# design.net
KiCad netlist of a schematic drawn in Altium Designer
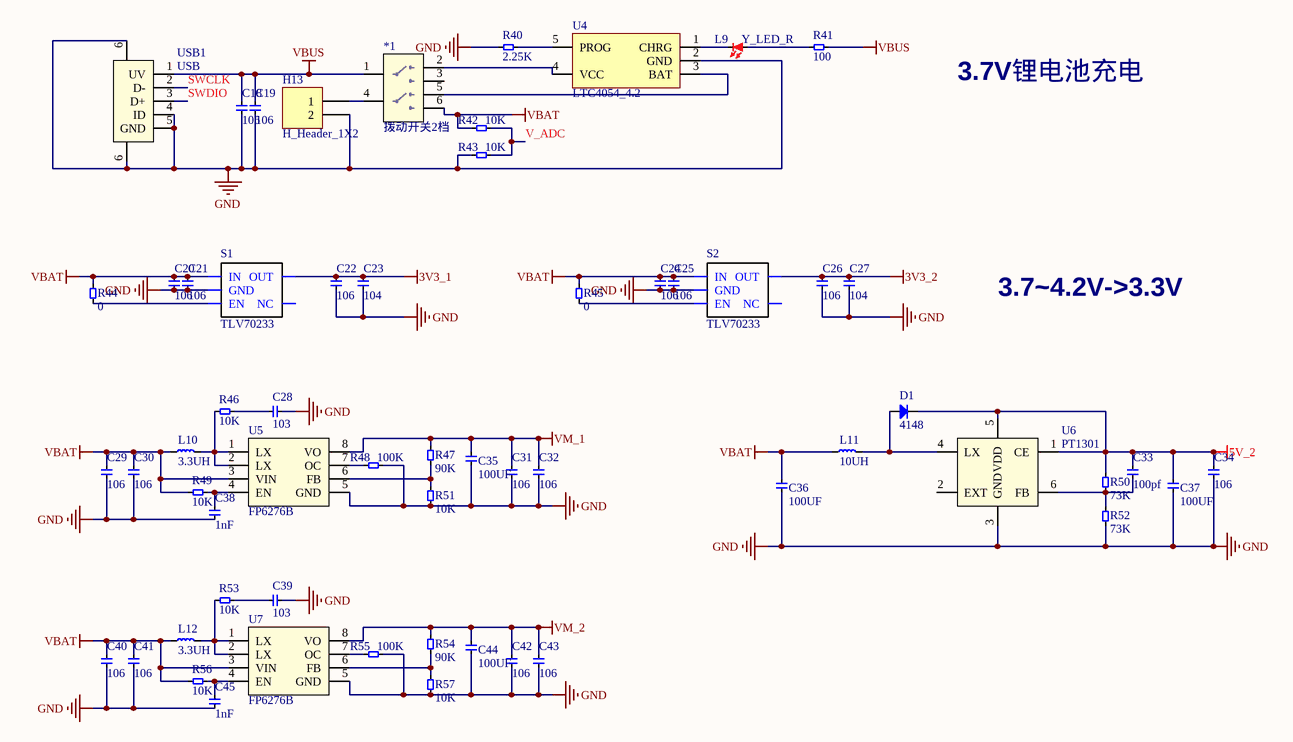
[diagram p0: 电源.SchDoc]

(export (version "E")
  (design (tool "Eeschema 10.0.6"))
  (components
    (comp (ref "*1") (value "拨动开关2档") (footprint "拨档开关2x3立式") (libsource (lib "王建勇") (part "拨动开关2档")))
    (comp (ref "C18")
      (value "106")
      (footprint "C_0603")
      (description "无极性贴片电容")
      (libsource (lib "电阻电容电感库") (part "C_无极贴片"))
    )
    (comp (ref "C19")
      (value "106")
      (footprint "C_0603")
      (description "无极性贴片电容")
      (libsource (lib "电阻电容电感库") (part "C_无极贴片"))
    )
    (comp (ref "C20")
      (value "106")
      (footprint "C_0603")
      (description "无极性贴片电容")
      (libsource (lib "电阻电容电感库") (part "C_无极贴片"))
    )
    (comp (ref "C21")
      (value "106")
      (footprint "C_0603")
      (description "无极性贴片电容")
      (libsource (lib "电阻电容电感库") (part "C_无极贴片"))
    )
    (comp (ref "C22")
      (value "106")
      (footprint "C_0603")
      (description "无极性贴片电容")
      (libsource (lib "电阻电容电感库") (part "C_无极贴片"))
    )
    (comp (ref "C23")
      (value "104")
      (footprint "C_0603")
      (description "无极性贴片电容")
      (libsource (lib "电阻电容电感库") (part "C_无极贴片"))
    )
    (comp (ref "C24")
      (value "106")
      (footprint "C_0603")
      (description "无极性贴片电容")
      (libsource (lib "电阻电容电感库") (part "C_无极贴片"))
    )
    (comp (ref "C25")
      (value "106")
      (footprint "C_0603")
      (description "无极性贴片电容")
      (libsource (lib "电阻电容电感库") (part "C_无极贴片"))
    )
    (comp (ref "C26")
      (value "106")
      (footprint "C_0603")
      (description "无极性贴片电容")
      (libsource (lib "电阻电容电感库") (part "C_无极贴片"))
    )
    (comp (ref "C27")
      (value "104")
      (footprint "C_0603")
      (description "无极性贴片电容")
      (libsource (lib "电阻电容电感库") (part "C_无极贴片"))
    )
    (comp (ref "C28")
      (value "103")
      (footprint "C_0603")
      (description "无极性贴片电容")
      (libsource (lib "电阻电容电感库") (part "C_无极贴片"))
    )
    (comp (ref "C29")
      (value "106")
      (footprint "C_0603")
      (description "无极性贴片电容")
      (libsource (lib "电阻电容电感库") (part "C_无极贴片"))
    )
    (comp (ref "C30")
      (value "106")
      (footprint "C_0603")
      (description "无极性贴片电容")
      (libsource (lib "电阻电容电感库") (part "C_无极贴片"))
    )
    (comp (ref "C31")
      (value "106")
      (footprint "C_0603")
      (description "无极性贴片电容")
      (libsource (lib "电阻电容电感库") (part "C_无极贴片"))
    )
    (comp (ref "C32")
      (value "106")
      (footprint "C_0603")
      (description "无极性贴片电容")
      (libsource (lib "电阻电容电感库") (part "C_无极贴片"))
    )
    (comp (ref "C33")
      (value "100pf")
      (footprint "C_0603")
      (description "无极性贴片电容")
      (libsource (lib "电阻电容电感库") (part "C_无极贴片"))
    )
    (comp (ref "C34")
      (value "106")
      (footprint "C_0603")
      (description "无极性贴片电容")
      (libsource (lib "电阻电容电感库") (part "C_无极贴片"))
    )
    (comp (ref "C35")
      (value "100UF")
      (footprint "C_1210")
      (description "无极性贴片电容")
      (libsource (lib "电阻电容电感库") (part "C_无极贴片"))
    )
    (comp (ref "C36")
      (value "100UF")
      (footprint "C_1210")
      (description "无极性贴片电容")
      (libsource (lib "电阻电容电感库") (part "C_无极贴片"))
    )
    (comp (ref "C37")
      (value "100UF")
      (footprint "C_1210")
      (description "无极性贴片电容")
      (libsource (lib "电阻电容电感库") (part "C_无极贴片"))
    )
    (comp (ref "C38")
      (value "1nF")
      (footprint "C_0603")
      (description "无极性贴片电容")
      (libsource (lib "电阻电容电感库") (part "C_无极贴片"))
    )
    (comp (ref "C39")
      (value "103")
      (footprint "C_0603")
      (description "无极性贴片电容")
      (libsource (lib "电阻电容电感库") (part "C_无极贴片"))
    )
    (comp (ref "C40")
      (value "106")
      (footprint "C_0603")
      (description "无极性贴片电容")
      (libsource (lib "电阻电容电感库") (part "C_无极贴片"))
    )
    (comp (ref "C41")
      (value "106")
      (footprint "C_0603")
      (description "无极性贴片电容")
      (libsource (lib "电阻电容电感库") (part "C_无极贴片"))
    )
    (comp (ref "C42")
      (value "106")
      (footprint "C_0603")
      (description "无极性贴片电容")
      (libsource (lib "电阻电容电感库") (part "C_无极贴片"))
    )
    (comp (ref "C43")
      (value "106")
      (footprint "C_0603")
      (description "无极性贴片电容")
      (libsource (lib "电阻电容电感库") (part "C_无极贴片"))
    )
    (comp (ref "C44")
      (value "100UF")
      (footprint "C_1210")
      (description "无极性贴片电容")
      (libsource (lib "电阻电容电感库") (part "C_无极贴片"))
    )
    (comp (ref "C45")
      (value "1nF")
      (footprint "C_0603")
      (description "无极性贴片电容")
      (libsource (lib "电阻电容电感库") (part "C_无极贴片"))
    )
    (comp (ref "D1")
      (value "4148")
      (footprint "1206D")
      (libsource (lib "lucifer-PCBLIB_V2.0（这是老蒋的）") (part "diode 4148"))
    )
    (comp (ref "H13")
      (value "H_Header_1X2")
      (footprint "H_Header_1X2")
      (description "单排2针排针")
      (fields (field (name "PUBLISHER") "Altium Limited"))
      (libsource (lib "接插件") (part "H_Header_1X2"))
    )
    (comp (ref "L9")
      (value "Y_LED_R")
      (footprint "Y_LED_0805_R")
      (description "红色LED")
      (libsource (lib "声光元件") (part "Y_LED_R"))
    )
    (comp (ref "L10")
      (value "3.3UH")
      (footprint "L_VISHAY_IHLP-1616")
      (description "贴片屏蔽式功率电感")
      (libsource (lib "电阻电容电感库") (part "L_贴片功率"))
    )
    (comp (ref "L11")
      (value "10UH")
      (footprint "L_VISHAY_IHLP-1616")
      (description "贴片屏蔽式功率电感")
      (libsource (lib "电阻电容电感库") (part "L_贴片功率"))
    )
    (comp (ref "L12")
      (value "3.3UH")
      (footprint "L_VISHAY_IHLP-1616")
      (description "贴片屏蔽式功率电感")
      (libsource (lib "电阻电容电感库") (part "L_贴片功率"))
    )
    (comp (ref "R40")
      (value "2.25K")
      (footprint "R_0603")
      (description "贴片电阻")
      (libsource (lib "电阻电容电感库") (part "R_贴片"))
    )
    (comp (ref "R41")
      (value "100")
      (footprint "R_0603")
      (description "贴片电阻")
      (libsource (lib "电阻电容电感库") (part "R_贴片"))
    )
    (comp (ref "R42")
      (value "10K")
      (footprint "R_0603")
      (description "贴片电阻")
      (libsource (lib "电阻电容电感库") (part "R_贴片"))
    )
    (comp (ref "R43")
      (value "10K")
      (footprint "R_0603")
      (description "贴片电阻")
      (libsource (lib "电阻电容电感库") (part "R_贴片"))
    )
    (comp (ref "R44")
      (value "0")
      (footprint "R_0603")
      (description "贴片电阻")
      (libsource (lib "电阻电容电感库") (part "R_贴片"))
    )
    (comp (ref "R45")
      (value "0")
      (footprint "R_0603")
      (description "贴片电阻")
      (libsource (lib "电阻电容电感库") (part "R_贴片"))
    )
    (comp (ref "R46")
      (value "10K")
      (footprint "R_0603")
      (description "贴片电阻")
      (libsource (lib "电阻电容电感库") (part "R_贴片"))
    )
    (comp (ref "R47")
      (value "90K")
      (footprint "R_0603")
      (description "贴片电阻")
      (libsource (lib "电阻电容电感库") (part "R_贴片"))
    )
    (comp (ref "R48")
      (value "100K")
      (footprint "R_0603")
      (description "贴片电阻")
      (libsource (lib "电阻电容电感库") (part "R_贴片"))
    )
    (comp (ref "R49")
      (value "10K")
      (footprint "R_0603")
      (description "贴片电阻")
      (libsource (lib "电阻电容电感库") (part "R_贴片"))
    )
    (comp (ref "R50")
      (value "73K")
      (footprint "R_0603")
      (description "贴片电阻")
      (libsource (lib "电阻电容电感库") (part "R_贴片"))
    )
    (comp (ref "R51")
      (value "10K")
      (footprint "R_0603")
      (description "贴片电阻")
      (libsource (lib "电阻电容电感库") (part "R_贴片"))
    )
    (comp (ref "R52")
      (value "73K")
      (footprint "R_0603")
      (description "贴片电阻")
      (libsource (lib "电阻电容电感库") (part "R_贴片"))
    )
    (comp (ref "R53")
      (value "10K")
      (footprint "R_0603")
      (description "贴片电阻")
      (libsource (lib "电阻电容电感库") (part "R_贴片"))
    )
    (comp (ref "R54")
      (value "90K")
      (footprint "R_0603")
      (description "贴片电阻")
      (libsource (lib "电阻电容电感库") (part "R_贴片"))
    )
    (comp (ref "R55")
      (value "100K")
      (footprint "R_0603")
      (description "贴片电阻")
      (libsource (lib "电阻电容电感库") (part "R_贴片"))
    )
    (comp (ref "R56")
      (value "10K")
      (footprint "R_0603")
      (description "贴片电阻")
      (libsource (lib "电阻电容电感库") (part "R_贴片"))
    )
    (comp (ref "R57")
      (value "10K")
      (footprint "R_0603")
      (description "贴片电阻")
      (libsource (lib "电阻电容电感库") (part "R_贴片"))
    )
    (comp (ref "S1")
      (value "TLV70233")
      (footprint "S_SOT23-5_TLV70233")
      (description "小封装LDO")
      (libsource (lib "电源") (part "S_TLV70233"))
    )
    (comp (ref "S2")
      (value "TLV70233")
      (footprint "S_SOT23-5_TLV70233")
      (description "小封装LDO")
      (libsource (lib "电源") (part "S_TLV70233"))
    )
    (comp (ref "U4") (value "LTC4054_4.2") (footprint "PDSO_G5") (libsource (lib "王建勇") (part "LTC4054_4.2")))
    (comp (ref "U5") (value "FP6276B") (footprint "SOP8") (libsource (lib "王建勇") (part "FP6267B")))
    (comp (ref "U6") (value "PT1301") (footprint "PDSO_G6") (libsource (lib "王建勇") (part "PT1301")))
    (comp (ref "U7") (value "FP6276B") (footprint "SOP8") (libsource (lib "王建勇") (part "FP6267B")))
    (comp (ref "USB1") (value "USB") (footprint "micro-USB(立式直插）") (libsource (lib "王建勇") (part "USB")))
  )
  (nets
    (net (code "1") (name "/SWCLK") (class "Default")
      (node (ref "USB1") (pin "2") (pinfunction "D-_2") (pintype "passive"))
    )
    (net (code "2") (name "/SWDIO") (class "Default")
      (node (ref "USB1") (pin "3") (pinfunction "D+_3") (pintype "passive"))
    )
    (net (code "3") (name "/V_ADC") (class "Default")
      (node (ref "R42") (pin "2") (pintype "passive"))
      (node (ref "R43") (pin "2") (pintype "passive"))
    )
    (net (code "4") (name "3V3_1") (class "Default")
      (node (ref "C22") (pin "2") (pinfunction "2_2") (pintype "passive"))
      (node (ref "C23") (pin "2") (pinfunction "2_2") (pintype "passive"))
      (node (ref "S1") (pin "5") (pinfunction "OUT_5") (pintype "passive"))
    )
    (net (code "5") (name "3V3_2") (class "Default")
      (node (ref "C26") (pin "2") (pinfunction "2_2") (pintype "passive"))
      (node (ref "C27") (pin "2") (pinfunction "2_2") (pintype "passive"))
      (node (ref "S2") (pin "5") (pinfunction "OUT_5") (pintype "passive"))
    )
    (net (code "6") (name "5V_2") (class "Default")
      (node (ref "C33") (pin "2") (pinfunction "2_2") (pintype "passive"))
      (node (ref "C34") (pin "2") (pinfunction "2_2") (pintype "passive"))
      (node (ref "C37") (pin "2") (pinfunction "2_2") (pintype "passive"))
      (node (ref "D1") (pin "2") (pinfunction "K_2") (pintype "passive"))
      (node (ref "R50") (pin "2") (pintype "passive"))
      (node (ref "U6") (pin "1") (pinfunction "CE_1") (pintype "passive"))
      (node (ref "U6") (pin "5") (pinfunction "VDD_5") (pintype "passive"))
    )
    (net (code "7") (name "GND") (class "Default")
      (node (ref "C18") (pin "1") (pinfunction "1_1") (pintype "passive"))
      (node (ref "C19") (pin "1") (pinfunction "1_1") (pintype "passive"))
      (node (ref "C20") (pin "1") (pinfunction "1_1") (pintype "passive"))
      (node (ref "C21") (pin "1") (pinfunction "1_1") (pintype "passive"))
      (node (ref "C22") (pin "1") (pinfunction "1_1") (pintype "passive"))
      (node (ref "C23") (pin "1") (pinfunction "1_1") (pintype "passive"))
      (node (ref "C24") (pin "1") (pinfunction "1_1") (pintype "passive"))
      (node (ref "C25") (pin "1") (pinfunction "1_1") (pintype "passive"))
      (node (ref "C26") (pin "1") (pinfunction "1_1") (pintype "passive"))
      (node (ref "C27") (pin "1") (pinfunction "1_1") (pintype "passive"))
      (node (ref "C28") (pin "2") (pinfunction "2_2") (pintype "passive"))
      (node (ref "C29") (pin "1") (pinfunction "1_1") (pintype "passive"))
      (node (ref "C30") (pin "1") (pinfunction "1_1") (pintype "passive"))
      (node (ref "C31") (pin "1") (pinfunction "1_1") (pintype "passive"))
      (node (ref "C32") (pin "1") (pinfunction "1_1") (pintype "passive"))
      (node (ref "C34") (pin "1") (pinfunction "1_1") (pintype "passive"))
      (node (ref "C35") (pin "1") (pinfunction "1_1") (pintype "passive"))
      (node (ref "C36") (pin "1") (pinfunction "1_1") (pintype "passive"))
      (node (ref "C37") (pin "1") (pinfunction "1_1") (pintype "passive"))
      (node (ref "C38") (pin "1") (pinfunction "1_1") (pintype "passive"))
      (node (ref "C39") (pin "2") (pinfunction "2_2") (pintype "passive"))
      (node (ref "C40") (pin "1") (pinfunction "1_1") (pintype "passive"))
      (node (ref "C41") (pin "1") (pinfunction "1_1") (pintype "passive"))
      (node (ref "C42") (pin "1") (pinfunction "1_1") (pintype "passive"))
      (node (ref "C43") (pin "1") (pinfunction "1_1") (pintype "passive"))
      (node (ref "C44") (pin "1") (pinfunction "1_1") (pintype "passive"))
      (node (ref "C45") (pin "1") (pinfunction "1_1") (pintype "passive"))
      (node (ref "H13") (pin "2") (pinfunction "2_2") (pintype "passive"))
      (node (ref "R40") (pin "1") (pintype "passive"))
      (node (ref "R43") (pin "1") (pintype "passive"))
      (node (ref "R48") (pin "2") (pintype "passive"))
      (node (ref "R51") (pin "1") (pintype "passive"))
      (node (ref "R52") (pin "1") (pintype "passive"))
      (node (ref "R55") (pin "2") (pintype "passive"))
      (node (ref "R57") (pin "1") (pintype "passive"))
      (node (ref "S1") (pin "2") (pinfunction "GND_2") (pintype "passive"))
      (node (ref "S2") (pin "2") (pinfunction "GND_2") (pintype "passive"))
      (node (ref "U4") (pin "2") (pinfunction "GND_2") (pintype "passive"))
      (node (ref "U5") (pin "5") (pinfunction "GND_5") (pintype "passive"))
      (node (ref "U6") (pin "3") (pinfunction "GND_3") (pintype "passive"))
      (node (ref "U7") (pin "5") (pinfunction "GND_5") (pintype "passive"))
      (node (ref "USB1") (pin "4") (pinfunction "ID_4") (pintype "passive"))
      (node (ref "USB1") (pin "5") (pinfunction "GND_5") (pintype "passive"))
      (node (ref "USB1") (pin "6") (pinfunction "G_6") (pintype "passive"))
    )
    (net (code "8") (name "Net-(*1-Pad4)") (class "Default")
      (node (ref "*1") (pin "4") (pintype "passive"))
      (node (ref "H13") (pin "1") (pinfunction "1_1") (pintype "passive"))
    )
    (net (code "9") (name "Net-(C28-Pad1)") (class "Default")
      (node (ref "C28") (pin "1") (pinfunction "1_1") (pintype "passive"))
      (node (ref "R46") (pin "2") (pintype "passive"))
    )
    (net (code "10") (name "Net-(C39-Pad1)") (class "Default")
      (node (ref "C39") (pin "1") (pinfunction "1_1") (pintype "passive"))
      (node (ref "R53") (pin "2") (pintype "passive"))
    )
    (net (code "11") (name "Net-(D1-A)") (class "Default")
      (node (ref "D1") (pin "1") (pinfunction "A_1") (pintype "passive"))
      (node (ref "L11") (pin "2") (pinfunction "2_2") (pintype "passive"))
      (node (ref "U6") (pin "4") (pinfunction "LX_4") (pintype "passive"))
    )
    (net (code "12") (name "Net-(L9-Pad1)") (class "Default")
      (node (ref "L9") (pin "1") (pintype "passive"))
      (node (ref "R41") (pin "1") (pintype "passive"))
    )
    (net (code "13") (name "Net-(L10-Pad2)") (class "Default")
      (node (ref "L10") (pin "2") (pinfunction "2_2") (pintype "passive"))
      (node (ref "R46") (pin "1") (pintype "passive"))
      (node (ref "U5") (pin "1") (pinfunction "LX_1") (pintype "passive"))
      (node (ref "U5") (pin "2") (pinfunction "LX_2") (pintype "passive"))
    )
    (net (code "14") (name "Net-(L12-Pad2)") (class "Default")
      (node (ref "L12") (pin "2") (pinfunction "2_2") (pintype "passive"))
      (node (ref "R53") (pin "1") (pintype "passive"))
      (node (ref "U7") (pin "1") (pinfunction "LX_1") (pintype "passive"))
      (node (ref "U7") (pin "2") (pinfunction "LX_2") (pintype "passive"))
    )
    (net (code "15") (name "Net-(S1-EN)") (class "Default")
      (node (ref "R44") (pin "1") (pintype "passive"))
      (node (ref "S1") (pin "3") (pinfunction "EN_3") (pintype "passive"))
    )
    (net (code "16") (name "Net-(S2-EN)") (class "Default")
      (node (ref "R45") (pin "1") (pintype "passive"))
      (node (ref "S2") (pin "3") (pinfunction "EN_3") (pintype "passive"))
    )
    (net (code "17") (name "Net-(U4-BAT)") (class "Default")
      (node (ref "*1") (pin "5") (pintype "passive"))
      (node (ref "U4") (pin "3") (pinfunction "BAT_3") (pintype "passive"))
    )
    (net (code "18") (name "Net-(U4-CHRG)") (class "Default")
      (node (ref "L9") (pin "2") (pintype "passive"))
      (node (ref "U4") (pin "1") (pinfunction "CHRG_1") (pintype "passive"))
    )
    (net (code "19") (name "Net-(U4-PROG)") (class "Default")
      (node (ref "R40") (pin "2") (pintype "passive"))
      (node (ref "U4") (pin "5") (pinfunction "PROG_5") (pintype "passive"))
    )
    (net (code "20") (name "Net-(U4-VCC)") (class "Default")
      (node (ref "*1") (pin "2") (pintype "passive"))
      (node (ref "U4") (pin "4") (pinfunction "VCC_4") (pintype "passive"))
    )
    (net (code "21") (name "Net-(U5-EN)") (class "Default")
      (node (ref "C38") (pin "2") (pinfunction "2_2") (pintype "passive"))
      (node (ref "R49") (pin "2") (pintype "passive"))
      (node (ref "U5") (pin "4") (pinfunction "EN_4") (pintype "passive"))
    )
    (net (code "22") (name "Net-(U5-FB)") (class "Default")
      (node (ref "R47") (pin "1") (pintype "passive"))
      (node (ref "R51") (pin "2") (pintype "passive"))
      (node (ref "U5") (pin "6") (pinfunction "FB_6") (pintype "passive"))
    )
    (net (code "23") (name "Net-(U5-OC)") (class "Default")
      (node (ref "R48") (pin "1") (pintype "passive"))
      (node (ref "U5") (pin "7") (pinfunction "OC_7") (pintype "passive"))
    )
    (net (code "24") (name "Net-(U6-FB)") (class "Default")
      (node (ref "C33") (pin "1") (pinfunction "1_1") (pintype "passive"))
      (node (ref "R50") (pin "1") (pintype "passive"))
      (node (ref "R52") (pin "2") (pintype "passive"))
      (node (ref "U6") (pin "6") (pinfunction "FB_6") (pintype "passive"))
    )
    (net (code "25") (name "Net-(U7-EN)") (class "Default")
      (node (ref "C45") (pin "2") (pinfunction "2_2") (pintype "passive"))
      (node (ref "R56") (pin "2") (pintype "passive"))
      (node (ref "U7") (pin "4") (pinfunction "EN_4") (pintype "passive"))
    )
    (net (code "26") (name "Net-(U7-FB)") (class "Default")
      (node (ref "R54") (pin "1") (pintype "passive"))
      (node (ref "R57") (pin "2") (pintype "passive"))
      (node (ref "U7") (pin "6") (pinfunction "FB_6") (pintype "passive"))
    )
    (net (code "27") (name "Net-(U7-OC)") (class "Default")
      (node (ref "R55") (pin "1") (pintype "passive"))
      (node (ref "U7") (pin "7") (pinfunction "OC_7") (pintype "passive"))
    )
    (net (code "28") (name "VBAT") (class "Default")
      (node (ref "*1") (pin "6") (pintype "passive"))
      (node (ref "C20") (pin "2") (pinfunction "2_2") (pintype "passive"))
      (node (ref "C21") (pin "2") (pinfunction "2_2") (pintype "passive"))
      (node (ref "C24") (pin "2") (pinfunction "2_2") (pintype "passive"))
      (node (ref "C25") (pin "2") (pinfunction "2_2") (pintype "passive"))
      (node (ref "C29") (pin "2") (pinfunction "2_2") (pintype "passive"))
      (node (ref "C30") (pin "2") (pinfunction "2_2") (pintype "passive"))
      (node (ref "C36") (pin "2") (pinfunction "2_2") (pintype "passive"))
      (node (ref "C40") (pin "2") (pinfunction "2_2") (pintype "passive"))
      (node (ref "C41") (pin "2") (pinfunction "2_2") (pintype "passive"))
      (node (ref "L10") (pin "1") (pinfunction "1_1") (pintype "passive"))
      (node (ref "L11") (pin "1") (pinfunction "1_1") (pintype "passive"))
      (node (ref "L12") (pin "1") (pinfunction "1_1") (pintype "passive"))
      (node (ref "R42") (pin "1") (pintype "passive"))
      (node (ref "R44") (pin "2") (pintype "passive"))
      (node (ref "R45") (pin "2") (pintype "passive"))
      (node (ref "R49") (pin "1") (pintype "passive"))
      (node (ref "R56") (pin "1") (pintype "passive"))
      (node (ref "S1") (pin "1") (pinfunction "IN_1") (pintype "passive"))
      (node (ref "S2") (pin "1") (pinfunction "IN_1") (pintype "passive"))
      (node (ref "U5") (pin "3") (pinfunction "VIN_3") (pintype "passive"))
      (node (ref "U7") (pin "3") (pinfunction "VIN_3") (pintype "passive"))
    )
    (net (code "29") (name "VBUS") (class "Default")
      (node (ref "*1") (pin "1") (pintype "passive"))
      (node (ref "C18") (pin "2") (pinfunction "2_2") (pintype "passive"))
      (node (ref "C19") (pin "2") (pinfunction "2_2") (pintype "passive"))
      (node (ref "R41") (pin "2") (pintype "passive"))
      (node (ref "USB1") (pin "1") (pinfunction "UV_1") (pintype "passive"))
    )
    (net (code "30") (name "VM_1") (class "Default")
      (node (ref "C31") (pin "2") (pinfunction "2_2") (pintype "passive"))
      (node (ref "C32") (pin "2") (pinfunction "2_2") (pintype "passive"))
      (node (ref "C35") (pin "2") (pinfunction "2_2") (pintype "passive"))
      (node (ref "R47") (pin "2") (pintype "passive"))
      (node (ref "U5") (pin "8") (pinfunction "VO_8") (pintype "passive"))
    )
    (net (code "31") (name "VM_2") (class "Default")
      (node (ref "C42") (pin "2") (pinfunction "2_2") (pintype "passive"))
      (node (ref "C43") (pin "2") (pinfunction "2_2") (pintype "passive"))
      (node (ref "C44") (pin "2") (pinfunction "2_2") (pintype "passive"))
      (node (ref "R54") (pin "2") (pintype "passive"))
      (node (ref "U7") (pin "8") (pinfunction "VO_8") (pintype "passive"))
    )
    (net (code "32") (name "unconnected-(*1-Pad3)") (class "Default")
      (node (ref "*1") (pin "3") (pintype "passive"))
    )
    (net (code "33") (name "unconnected-(S1-NC-Pad4)") (class "Default")
      (node (ref "S1") (pin "4") (pinfunction "NC_4") (pintype "passive"))
    )
    (net (code "34") (name "unconnected-(S2-NC-Pad4)") (class "Default")
      (node (ref "S2") (pin "4") (pinfunction "NC_4") (pintype "passive"))
    )
    (net (code "35") (name "unconnected-(U6-EXT-Pad2)") (class "Default")
      (node (ref "U6") (pin "2") (pinfunction "EXT_2") (pintype "passive"))
    )
  )
)
